# H_bridge.net
KiCad netlist of a schematic drawn in Altium Designer
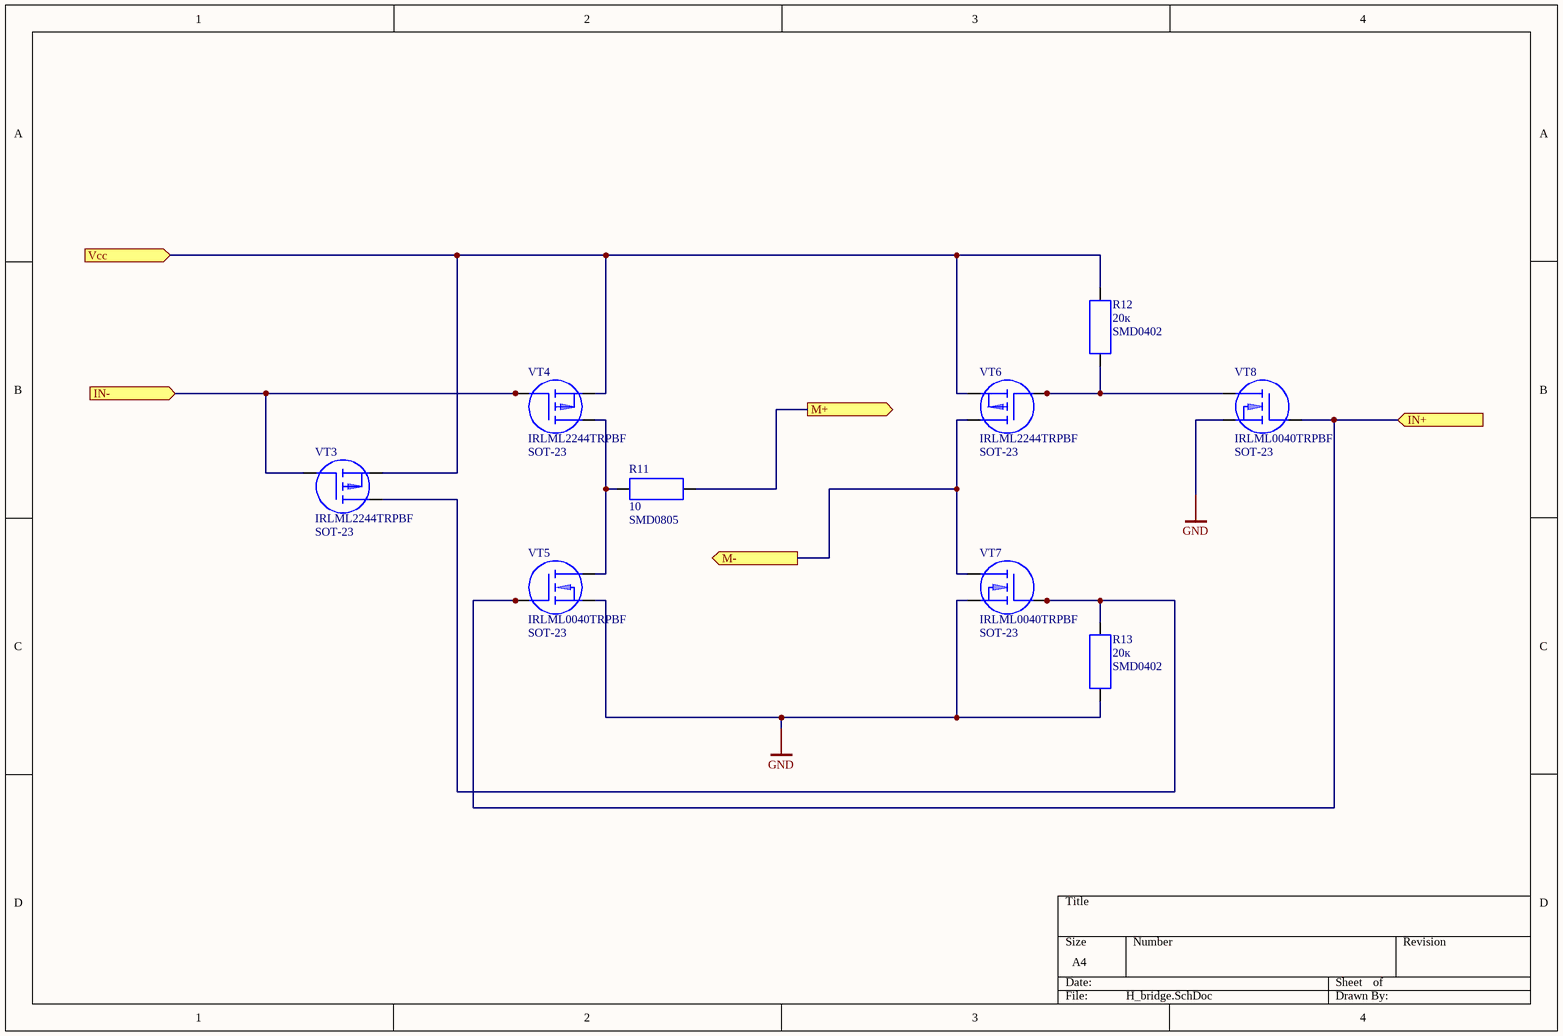
[diagram p0: H_bridge.SchDoc]

(export (version "E")
  (design (tool "Eeschema 10.0.6"))
  (components
    (comp (ref "R11")
      (value "10")
      (footprint "SMD0805(2012)")
      (fields (field (name "PACKAGE") "SMD0805"))
      (libsource (lib "MechanikLibrary") (part "R_0805"))
    )
    (comp (ref "R12")
      (value "20к")
      (footprint "SMD0402(1608)")
      (fields (field (name "PACKAGE") "SMD0402"))
      (libsource (lib "MechanikLibrary") (part "R_0402"))
    )
    (comp (ref "R13")
      (value "20к")
      (footprint "SMD0402(1608)")
      (fields (field (name "PACKAGE") "SMD0402"))
      (libsource (lib "MechanikLibrary") (part "R_0402"))
    )
    (comp (ref "VT3")
      (value "IRLML2244TRPBF")
      (footprint "SOT23-3")
      (fields (field (name "PACKAGE") "SOT-23"))
      (libsource (lib "MechanikLibrary") (part "VT_P_MOSFET_SOT23_3"))
    )
    (comp (ref "VT4")
      (value "IRLML2244TRPBF")
      (footprint "SOT23-3")
      (fields (field (name "PACKAGE") "SOT-23"))
      (libsource (lib "MechanikLibrary") (part "VT_P_MOSFET_SOT23_3"))
    )
    (comp (ref "VT5")
      (value "IRLML0040TRPBF")
      (footprint "SOT23-3")
      (fields (field (name "PACKAGE") "SOT-23"))
      (libsource (lib "MechanikLibrary") (part "VT_N_MOSFET_SOT23_3"))
    )
    (comp (ref "VT6")
      (value "IRLML2244TRPBF")
      (footprint "SOT23-3")
      (fields (field (name "PACKAGE") "SOT-23"))
      (libsource (lib "MechanikLibrary") (part "VT_P_MOSFET_SOT23_3"))
    )
    (comp (ref "VT7")
      (value "IRLML0040TRPBF")
      (footprint "SOT23-3")
      (fields (field (name "PACKAGE") "SOT-23"))
      (libsource (lib "MechanikLibrary") (part "VT_N_MOSFET_SOT23_3"))
    )
    (comp (ref "VT8")
      (value "IRLML0040TRPBF")
      (footprint "SOT23-3")
      (fields (field (name "PACKAGE") "SOT-23"))
      (libsource (lib "MechanikLibrary") (part "VT_N_MOSFET_SOT23_3"))
    )
  )
  (nets
    (net (code "1") (name "/IN+") (class "Default")
      (node (ref "VT5") (pin "1") (pintype "passive"))
      (node (ref "VT8") (pin "1") (pintype "passive"))
    )
    (net (code "2") (name "/IN-") (class "Default")
      (node (ref "VT3") (pin "1") (pintype "passive"))
      (node (ref "VT4") (pin "1") (pintype "passive"))
    )
    (net (code "3") (name "/M+") (class "Default") (node (ref "R11") (pin "1") (pintype "passive")))
    (net (code "4") (name "/M-") (class "Default")
      (node (ref "VT6") (pin "3") (pintype "passive"))
      (node (ref "VT7") (pin "3") (pintype "passive"))
    )
    (net (code "5") (name "/Vcc") (class "Default")
      (node (ref "R12") (pin "1") (pintype "passive"))
      (node (ref "VT3") (pin "2") (pintype "passive"))
      (node (ref "VT4") (pin "2") (pintype "passive"))
      (node (ref "VT6") (pin "2") (pintype "passive"))
    )
    (net (code "6") (name "GND") (class "Default")
      (node (ref "R13") (pin "2") (pintype "passive"))
      (node (ref "VT5") (pin "2") (pintype "passive"))
      (node (ref "VT7") (pin "2") (pintype "passive"))
      (node (ref "VT8") (pin "2") (pintype "passive"))
    )
    (net (code "7") (name "Net-(R11-Pad2)") (class "Default")
      (node (ref "R11") (pin "2") (pintype "passive"))
      (node (ref "VT4") (pin "3") (pintype "passive"))
      (node (ref "VT5") (pin "3") (pintype "passive"))
    )
    (net (code "8") (name "Net-(R12-Pad2)") (class "Default")
      (node (ref "R12") (pin "2") (pintype "passive"))
      (node (ref "VT6") (pin "1") (pintype "passive"))
      (node (ref "VT8") (pin "3") (pintype "passive"))
    )
    (net (code "9") (name "Net-(R13-Pad1)") (class "Default")
      (node (ref "R13") (pin "1") (pintype "passive"))
      (node (ref "VT3") (pin "3") (pintype "passive"))
      (node (ref "VT7") (pin "1") (pintype "passive"))
    )
  )
)
